# USB_CY7C68001-56LFC.net
KiCad netlist of a schematic drawn in Altium Designer
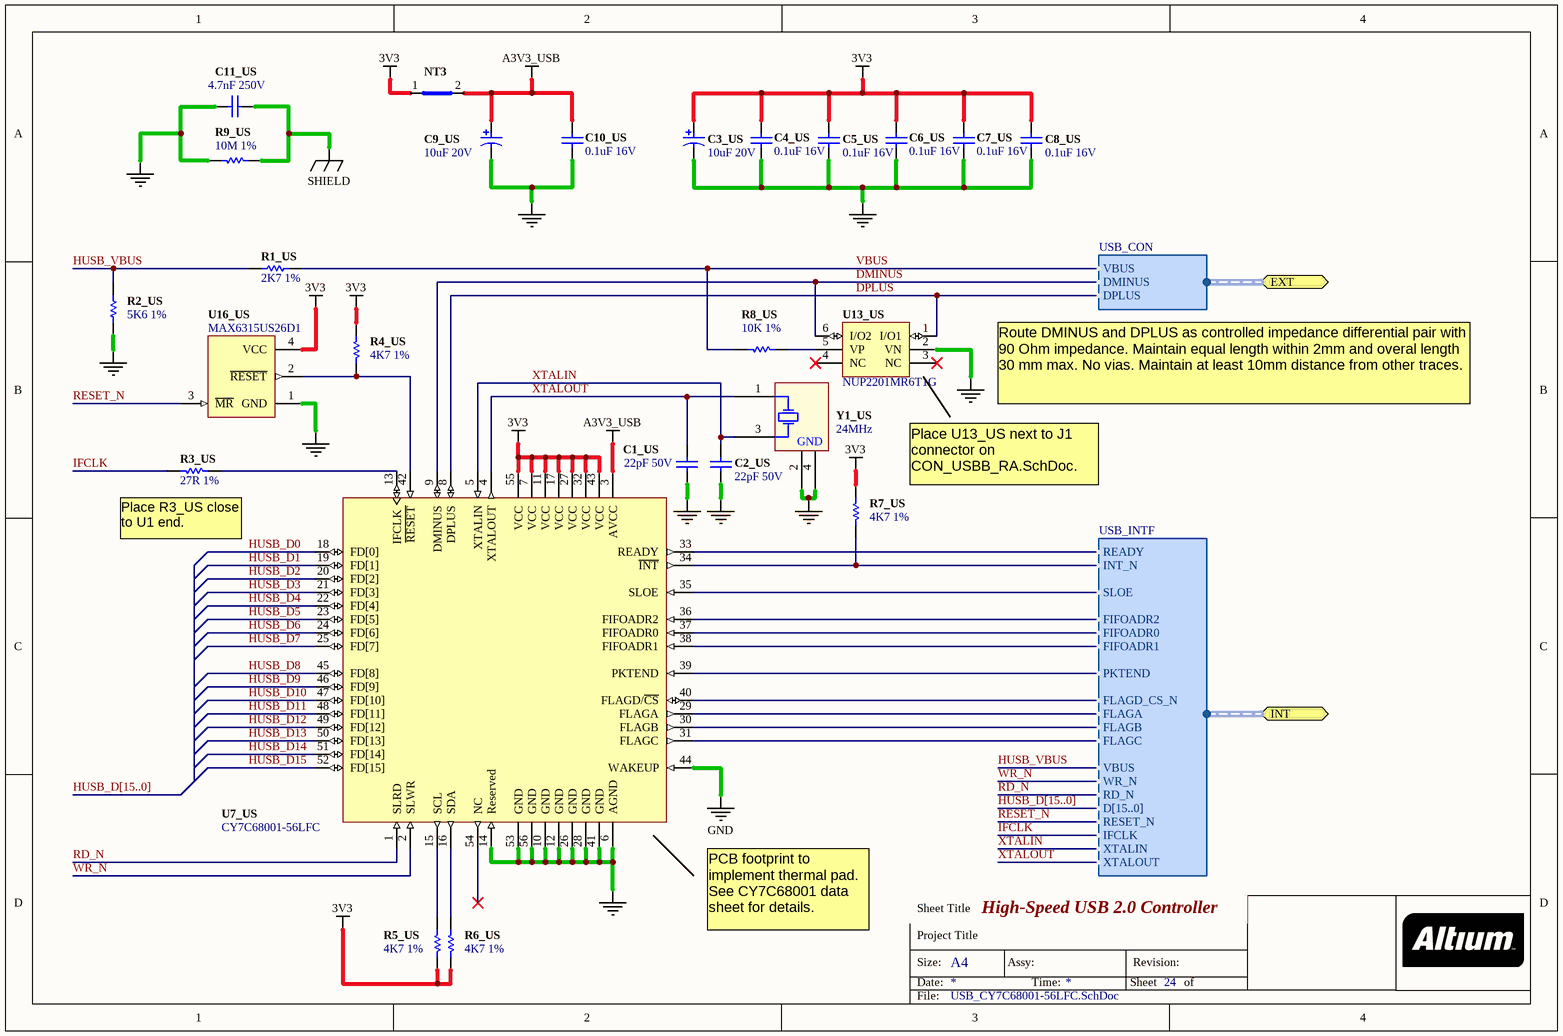
[diagram p0: USB_CY7C68001-56LFC.SchDoc]

(export (version "E")
  (design (tool "Eeschema 10.0.6"))
  (components
    (comp (ref "C1_US")
      (value "22pF 50V")
      (footprint "CAPC1005-STAR")
      (description "Capacitor, Ceramic, 22pF 5% 50V 0402 (1005) COG")
      (fields (field (name "TOLERANCE") "5 %"))
      (libsource (lib "AltiumDesignLibrary") (part "CAP-NP"))
    )
    (comp (ref "C2_US")
      (value "22pF 50V")
      (footprint "CAPC1005-STAR")
      (description "Capacitor, Ceramic, 22pF 5% 50V 0402 (1005) COG")
      (fields (field (name "TOLERANCE") "5 %"))
      (libsource (lib "AltiumDesignLibrary") (part "CAP-NP"))
    )
    (comp (ref "C3_US")
      (value "10uF 20V")
      (footprint "CAPC3528-STAR")
      (description "Capacitor, Tantalum, 10uF 10% 20V MCCT-B (3528)")
      (fields (field (name "TOLERANCE") "10 %"))
      (libsource (lib "AltiumDesignLibrary") (part "CAP-P"))
    )
    (comp (ref "C4_US")
      (value "0.1uF 16V")
      (footprint "CAPC1005-STAR")
      (description "Capacitor, Ceramic, 0.1uF 10% 16V 0402 (1005) X7R")
      (fields (field (name "TOLERANCE") "10 %"))
      (libsource (lib "AltiumDesignLibrary") (part "CAP-NP"))
    )
    (comp (ref "C5_US")
      (value "0.1uF 16V")
      (footprint "CAPC1005-STAR")
      (description "Capacitor, Ceramic, 0.1uF 10% 16V 0402 (1005) X7R")
      (fields (field (name "TOLERANCE") "10 %"))
      (libsource (lib "AltiumDesignLibrary") (part "CAP-NP"))
    )
    (comp (ref "C6_US")
      (value "0.1uF 16V")
      (footprint "CAPC1005-STAR")
      (description "Capacitor, Ceramic, 0.1uF 10% 16V 0402 (1005) X7R")
      (fields (field (name "TOLERANCE") "10 %"))
      (libsource (lib "AltiumDesignLibrary") (part "CAP-NP"))
    )
    (comp (ref "C7_US")
      (value "0.1uF 16V")
      (footprint "CAPC1005-STAR")
      (description "Capacitor, Ceramic, 0.1uF 10% 16V 0402 (1005) X7R")
      (fields (field (name "TOLERANCE") "10 %"))
      (libsource (lib "AltiumDesignLibrary") (part "CAP-NP"))
    )
    (comp (ref "C8_US")
      (value "0.1uF 16V")
      (footprint "CAPC1005-STAR")
      (description "Capacitor, Ceramic, 0.1uF 10% 16V 0402 (1005) X7R")
      (fields (field (name "TOLERANCE") "10 %"))
      (libsource (lib "AltiumDesignLibrary") (part "CAP-NP"))
    )
    (comp (ref "C9_US")
      (value "10uF 20V")
      (footprint "CAPC3528-STAR")
      (description "Capacitor, Tantalum, 10uF 10% 20V MCCT-B (3528)")
      (fields (field (name "TOLERANCE") "10 %"))
      (libsource (lib "AltiumDesignLibrary") (part "CAP-P"))
    )
    (comp (ref "C10_US")
      (value "0.1uF 16V")
      (footprint "CAPC1005-STAR")
      (description "Capacitor, Ceramic, 0.1uF 10% 16V 0402 (1005) X7R")
      (fields (field (name "TOLERANCE") "10 %"))
      (libsource (lib "AltiumDesignLibrary") (part "CAP-NP"))
    )
    (comp (ref "C11_US")
      (value "4.7nF 250V")
      (footprint "CAPM7163")
      (description "Capacitor, Ceramic, 4.7nF 20% 250V Panasonic BC J Lead (CAPM7163) Y5V")
      (fields (field (name "TOLERANCE") "20% %"))
      (libsource (lib "AltiumDesignLibrary") (part "CAP-NP"))
    )
    (comp (ref "NT3")
      (value "Net Tie SMT2")
      (footprint "NETTIE-SMT2-31X51")
      (description "Net-Tie, Surface Mount, 2 x 1.6mm x 0.8mm SMT Pads - For 0.8mm Track")
      (libsource (lib "AltiumDesignLibrary") (part "NETTIE-SMT2"))
    )
    (comp (ref "R1_US")
      (value "2K7 1%")
      (footprint "RESC1005-STAR")
      (description "Resistor, 2K7 1% 0402 (1005)")
      (fields (field (name "TOLERANCE") "1 %"))
      (libsource (lib "AltiumDesignLibrary") (part "RES"))
    )
    (comp (ref "R2_US")
      (value "5K6 1%")
      (footprint "RESC1005-STAR")
      (description "Resistor, 5K6 1% 0402 (1005)")
      (fields (field (name "TOLERANCE") "1 %"))
      (libsource (lib "AltiumDesignLibrary") (part "RES"))
    )
    (comp (ref "R3_US")
      (value "27R 1%")
      (footprint "RESC1005-STAR")
      (description "Resistor, 27R 1% 0402 (1005)")
      (fields (field (name "TOLERANCE") "1 %"))
      (libsource (lib "AltiumDesignLibrary") (part "RES"))
    )
    (comp (ref "R4_US")
      (value "4K7 1%")
      (footprint "RESC1005-STAR")
      (description "Resistor, 4K7 1% 0402 (1005)")
      (fields (field (name "TOLERANCE") "1 %"))
      (libsource (lib "AltiumDesignLibrary") (part "RES"))
    )
    (comp (ref "R5_US")
      (value "4K7 1%")
      (footprint "RESC1005-STAR")
      (description "Resistor, 4K7 1% 0402 (1005)")
      (fields (field (name "TOLERANCE") "1 %"))
      (libsource (lib "AltiumDesignLibrary") (part "RES"))
    )
    (comp (ref "R6_US")
      (value "4K7 1%")
      (footprint "RESC1005-STAR")
      (description "Resistor, 4K7 1% 0402 (1005)")
      (fields (field (name "TOLERANCE") "1 %"))
      (libsource (lib "AltiumDesignLibrary") (part "RES"))
    )
    (comp (ref "R7_US")
      (value "4K7 1%")
      (footprint "RESC1005-STAR")
      (description "Resistor, 4K7 1% 0402 (1005)")
      (fields (field (name "TOLERANCE") "1 %"))
      (libsource (lib "AltiumDesignLibrary") (part "RES"))
    )
    (comp (ref "R8_US")
      (value "10K 1%")
      (footprint "RESC1005-STAR")
      (description "Resistor, 10K 1% 0402 (1005)")
      (fields (field (name "TOLERANCE") "1 %"))
      (libsource (lib "AltiumDesignLibrary") (part "RES"))
    )
    (comp (ref "R9_US")
      (value "10M 1%")
      (footprint "RESC3216")
      (description "Resistor, 10M 1%1206 (3216)")
      (fields (field (name "TOLERANCE") "1 %"))
      (libsource (lib "AltiumDesignLibrary") (part "RES"))
    )
    (comp (ref "U7_US")
      (value "CY7C68001-56LFC")
      (footprint "QFN50P800X800_HS-57")
      (description "CY7C68001-56LFC, EZ-USB SX2 High-Speed USB Interface")
      (libsource (lib "AltiumDesignLibrary") (part "CY7C68001-56LFC"))
    )
    (comp (ref "U13_US")
      (value "NUP2201MR6T1G")
      (footprint "TSOP95P275-6")
      (description "NUP2201MR6, Low Capacitance Diode Array, USB Protection")
      (libsource (lib "AltiumDesignLibrary") (part "NUP2201MR6"))
    )
    (comp (ref "U16_US")
      (value "MAX6315US26D1")
      (footprint "SOT143")
      (description "MAX6315, Open-Drain Output SOT Reset IC, Customized Reset Thresholds, Timeout Delays")
      (libsource (lib "AltiumDesignLibrary") (part "MAX6315"))
    )
    (comp (ref "Y1_US")
      (value "24MHz")
      (footprint "XTAL-200X126-4")
      (description "Crystal, SMD, 24.000000MHz Stab=30ppm 20.0pF")
      (libsource (lib "AltiumDesignLibrary") (part "CRYSTAL-200X126-4"))
    )
  )
  (nets
    (net (code "3") (name "/DMINUS") (class "Default")
      (node (ref "U13_US") (pin "6") (pinfunction "I/O2_6") (pintype "bidirectional"))
      (node (ref "U7_US") (pin "9") (pinfunction "DMINUS_9") (pintype "bidirectional"))
    )
    (net (code "4") (name "/DPLUS") (class "Default")
      (node (ref "U13_US") (pin "1") (pinfunction "I/O1_1") (pintype "bidirectional"))
      (node (ref "U7_US") (pin "8") (pinfunction "DPLUS_8") (pintype "bidirectional"))
    )
    (net (code "5") (name "/FIFOADR0") (class "Default")
      (node (ref "U7_US") (pin "37") (pinfunction "FIFOADR0_37") (pintype "input"))
    )
    (net (code "6") (name "/FIFOADR1") (class "Default")
      (node (ref "U7_US") (pin "38") (pinfunction "FIFOADR1_38") (pintype "input"))
    )
    (net (code "7") (name "/FIFOADR2") (class "Default")
      (node (ref "U7_US") (pin "36") (pinfunction "FIFOADR2_36") (pintype "input"))
    )
    (net (code "8") (name "/FLAGA") (class "Default")
      (node (ref "U7_US") (pin "29") (pinfunction "FLAGA_29") (pintype "output"))
    )
    (net (code "9") (name "/FLAGB") (class "Default")
      (node (ref "U7_US") (pin "30") (pinfunction "FLAGB_30") (pintype "output"))
    )
    (net (code "10") (name "/FLAGC") (class "Default")
      (node (ref "U7_US") (pin "31") (pinfunction "FLAGC_31") (pintype "output"))
    )
    (net (code "11") (name "/FLAGD_CS_N") (class "Default")
      (node (ref "U7_US") (pin "40") (pinfunction "FLAGD/~{CS}_40") (pintype "bidirectional"))
    )
    (net (code "12") (name "/HUSB_D0") (class "Default")
      (node (ref "U7_US") (pin "18") (pinfunction "FD[0]_18") (pintype "bidirectional"))
    )
    (net (code "13") (name "/HUSB_D1") (class "Default")
      (node (ref "U7_US") (pin "19") (pinfunction "FD[1]_19") (pintype "bidirectional"))
    )
    (net (code "14") (name "/HUSB_D2") (class "Default")
      (node (ref "U7_US") (pin "20") (pinfunction "FD[2]_20") (pintype "bidirectional"))
    )
    (net (code "15") (name "/HUSB_D3") (class "Default")
      (node (ref "U7_US") (pin "21") (pinfunction "FD[3]_21") (pintype "bidirectional"))
    )
    (net (code "16") (name "/HUSB_D4") (class "Default")
      (node (ref "U7_US") (pin "22") (pinfunction "FD[4]_22") (pintype "bidirectional"))
    )
    (net (code "17") (name "/HUSB_D5") (class "Default")
      (node (ref "U7_US") (pin "23") (pinfunction "FD[5]_23") (pintype "bidirectional"))
    )
    (net (code "18") (name "/HUSB_D6") (class "Default")
      (node (ref "U7_US") (pin "24") (pinfunction "FD[6]_24") (pintype "bidirectional"))
    )
    (net (code "19") (name "/HUSB_D7") (class "Default")
      (node (ref "U7_US") (pin "25") (pinfunction "FD[7]_25") (pintype "bidirectional"))
    )
    (net (code "20") (name "/HUSB_D8") (class "Default")
      (node (ref "U7_US") (pin "45") (pinfunction "FD[8]_45") (pintype "bidirectional"))
    )
    (net (code "21") (name "/HUSB_D9") (class "Default")
      (node (ref "U7_US") (pin "46") (pinfunction "FD[9]_46") (pintype "bidirectional"))
    )
    (net (code "22") (name "/HUSB_D10") (class "Default")
      (node (ref "U7_US") (pin "47") (pinfunction "FD[10]_47") (pintype "bidirectional"))
    )
    (net (code "23") (name "/HUSB_D11") (class "Default")
      (node (ref "U7_US") (pin "48") (pinfunction "FD[11]_48") (pintype "bidirectional"))
    )
    (net (code "24") (name "/HUSB_D12") (class "Default")
      (node (ref "U7_US") (pin "49") (pinfunction "FD[12]_49") (pintype "bidirectional"))
    )
    (net (code "25") (name "/HUSB_D13") (class "Default")
      (node (ref "U7_US") (pin "50") (pinfunction "FD[13]_50") (pintype "bidirectional"))
    )
    (net (code "26") (name "/HUSB_D14") (class "Default")
      (node (ref "U7_US") (pin "51") (pinfunction "FD[14]_51") (pintype "bidirectional"))
    )
    (net (code "27") (name "/HUSB_D15") (class "Default")
      (node (ref "U7_US") (pin "52") (pinfunction "FD[15]_52") (pintype "bidirectional"))
    )
    (net (code "29") (name "/HUSB_VBUS") (class "Default")
      (node (ref "R1_US") (pin "1") (pinfunction "1_1") (pintype "passive"))
      (node (ref "R2_US") (pin "1") (pinfunction "1_1") (pintype "passive"))
    )
    (net (code "30") (name "/IFCLK") (class "Default")
      (node (ref "R3_US") (pin "1") (pinfunction "1_1") (pintype "passive"))
    )
    (net (code "31") (name "/INT_N") (class "Default")
      (node (ref "R7_US") (pin "1") (pinfunction "1_1") (pintype "passive"))
      (node (ref "U7_US") (pin "34") (pinfunction "~{INT}_34") (pintype "output"))
    )
    (net (code "32") (name "/PKTEND") (class "Default")
      (node (ref "U7_US") (pin "39") (pinfunction "PKTEND_39") (pintype "input"))
    )
    (net (code "33") (name "/RD_N") (class "Default")
      (node (ref "U7_US") (pin "1") (pinfunction "SLRD_1") (pintype "input"))
    )
    (net (code "34") (name "/READY") (class "Default")
      (node (ref "U7_US") (pin "33") (pinfunction "READY_33") (pintype "output"))
    )
    (net (code "35") (name "/RESET_N") (class "Default")
      (node (ref "U16_US") (pin "3") (pinfunction "~{MR}_3") (pintype "input"))
    )
    (net (code "36") (name "/SLOE") (class "Default")
      (node (ref "U7_US") (pin "35") (pinfunction "SLOE_35") (pintype "input"))
    )
    (net (code "37") (name "/VBUS") (class "Default")
      (node (ref "R1_US") (pin "2") (pinfunction "2_2") (pintype "passive"))
      (node (ref "R8_US") (pin "1") (pinfunction "1_1") (pintype "passive"))
    )
    (net (code "38") (name "/WR_N") (class "Default")
      (node (ref "U7_US") (pin "2") (pinfunction "SLWR_2") (pintype "input"))
    )
    (net (code "39") (name "/XTALIN") (class "Default")
      (node (ref "C2_US") (pin "1") (pinfunction "1_1") (pintype "passive"))
      (node (ref "U7_US") (pin "5") (pinfunction "XTALIN_5") (pintype "input"))
      (node (ref "Y1_US") (pin "3") (pinfunction "X2_3") (pintype "passive"))
    )
    (net (code "40") (name "/XTALOUT") (class "Default")
      (node (ref "C1_US") (pin "1") (pinfunction "1_1") (pintype "passive"))
      (node (ref "U7_US") (pin "4") (pinfunction "XTALOUT_4") (pintype "output"))
      (node (ref "Y1_US") (pin "1") (pinfunction "X1_1") (pintype "passive"))
    )
    (net (code "43") (name "3V3") (class "Default")
      (node (ref "C3_US") (pin "1") (pinfunction "1_1") (pintype "passive"))
      (node (ref "C4_US") (pin "2") (pinfunction "2_2") (pintype "passive"))
      (node (ref "C5_US") (pin "1") (pinfunction "1_1") (pintype "passive"))
      (node (ref "C6_US") (pin "2") (pinfunction "2_2") (pintype "passive"))
      (node (ref "C7_US") (pin "2") (pinfunction "2_2") (pintype "passive"))
      (node (ref "C8_US") (pin "1") (pinfunction "1_1") (pintype "passive"))
      (node (ref "NT3") (pin "1") (pinfunction "Net1_1") (pintype "passive"))
      (node (ref "R4_US") (pin "2") (pinfunction "2_2") (pintype "passive"))
      (node (ref "R5_US") (pin "1") (pinfunction "1_1") (pintype "passive"))
      (node (ref "R6_US") (pin "1") (pinfunction "1_1") (pintype "passive"))
      (node (ref "R7_US") (pin "2") (pinfunction "2_2") (pintype "passive"))
      (node (ref "U16_US") (pin "4") (pinfunction "VCC_4") (pintype "power_in"))
      (node (ref "U7_US") (pin "11") (pinfunction "VCC_11") (pintype "power_in"))
      (node (ref "U7_US") (pin "17") (pinfunction "VCC_17") (pintype "power_in"))
      (node (ref "U7_US") (pin "27") (pinfunction "VCC_27") (pintype "power_in"))
      (node (ref "U7_US") (pin "32") (pinfunction "VCC_32") (pintype "power_in"))
      (node (ref "U7_US") (pin "43") (pinfunction "VCC_43") (pintype "power_in"))
      (node (ref "U7_US") (pin "55") (pinfunction "VCC_55") (pintype "power_in"))
      (node (ref "U7_US") (pin "7") (pinfunction "VCC_7") (pintype "power_in"))
    )
    (net (code "44") (name "A3V3_USB") (class "Default")
      (node (ref "C10_US") (pin "2") (pinfunction "2_2") (pintype "passive"))
      (node (ref "C9_US") (pin "1") (pinfunction "1_1") (pintype "passive"))
      (node (ref "NT3") (pin "2") (pinfunction "Net2_2") (pintype "passive"))
      (node (ref "U7_US") (pin "3") (pinfunction "AVCC_3") (pintype "power_in"))
    )
    (net (code "45") (name "GND") (class "Default")
      (node (ref "C10_US") (pin "1") (pinfunction "1_1") (pintype "passive"))
      (node (ref "C11_US") (pin "2") (pinfunction "2_2") (pintype "passive"))
      (node (ref "C1_US") (pin "2") (pinfunction "2_2") (pintype "passive"))
      (node (ref "C2_US") (pin "2") (pinfunction "2_2") (pintype "passive"))
      (node (ref "C3_US") (pin "2") (pinfunction "2_2") (pintype "passive"))
      (node (ref "C4_US") (pin "1") (pinfunction "1_1") (pintype "passive"))
      (node (ref "C5_US") (pin "2") (pinfunction "2_2") (pintype "passive"))
      (node (ref "C6_US") (pin "1") (pinfunction "1_1") (pintype "passive"))
      (node (ref "C7_US") (pin "1") (pinfunction "1_1") (pintype "passive"))
      (node (ref "C8_US") (pin "2") (pinfunction "2_2") (pintype "passive"))
      (node (ref "C9_US") (pin "2") (pinfunction "2_2") (pintype "passive"))
      (node (ref "R2_US") (pin "2") (pinfunction "2_2") (pintype "passive"))
      (node (ref "R9_US") (pin "2") (pinfunction "2_2") (pintype "passive"))
      (node (ref "U13_US") (pin "2") (pinfunction "VN_2") (pintype "power_in"))
      (node (ref "U16_US") (pin "1") (pinfunction "GND_1") (pintype "power_in"))
      (node (ref "U7_US") (pin "10") (pinfunction "GND_10") (pintype "power_in"))
      (node (ref "U7_US") (pin "12") (pinfunction "GND_12") (pintype "power_in"))
      (node (ref "U7_US") (pin "14") (pinfunction "Reserved_14") (pintype "input"))
      (node (ref "U7_US") (pin "26") (pinfunction "GND_26") (pintype "power_in"))
      (node (ref "U7_US") (pin "28") (pinfunction "GND_28") (pintype "power_in"))
      (node (ref "U7_US") (pin "41") (pinfunction "GND_41") (pintype "power_in"))
      (node (ref "U7_US") (pin "44") (pinfunction "WAKEUP_44") (pintype "input"))
      (node (ref "U7_US") (pin "53") (pinfunction "GND_53") (pintype "power_in"))
      (node (ref "U7_US") (pin "56") (pinfunction "GND_56") (pintype "power_in"))
      (node (ref "U7_US") (pin "6") (pinfunction "AGND_6") (pintype "power_in"))
      (node (ref "Y1_US") (pin "2") (pinfunction "GND_2") (pintype "passive"))
      (node (ref "Y1_US") (pin "4") (pinfunction "GND_4") (pintype "passive"))
    )
    (net (code "46") (name "Net-(U7_US-IFCLK)") (class "Default")
      (node (ref "R3_US") (pin "2") (pinfunction "2_2") (pintype "passive"))
      (node (ref "U7_US") (pin "13") (pinfunction "IFCLK_13") (pintype "bidirectional"))
    )
    (net (code "47") (name "Net-(U7_US-SCL)") (class "Default")
      (node (ref "R5_US") (pin "2") (pinfunction "2_2") (pintype "passive"))
      (node (ref "U7_US") (pin "15") (pinfunction "SCL_15") (pintype "output"))
    )
    (net (code "48") (name "Net-(U7_US-SDA)") (class "Default")
      (node (ref "R6_US") (pin "2") (pinfunction "2_2") (pintype "passive"))
      (node (ref "U7_US") (pin "16") (pinfunction "SDA_16") (pintype "output"))
    )
    (net (code "49") (name "Net-(U13_US-VP)") (class "Default")
      (node (ref "R8_US") (pin "2") (pinfunction "2_2") (pintype "passive"))
      (node (ref "U13_US") (pin "5") (pinfunction "VP_5") (pintype "power_in"))
    )
    (net (code "50") (name "Net-(U16_US-~{RESET})") (class "Default")
      (node (ref "R4_US") (pin "1") (pinfunction "1_1") (pintype "passive"))
      (node (ref "U16_US") (pin "2") (pinfunction "~{RESET}_2") (pintype "output"))
      (node (ref "U7_US") (pin "42") (pinfunction "~{RESET}_42") (pintype "input"))
    )
    (net (code "51") (name "SHIELD") (class "Default")
      (node (ref "C11_US") (pin "1") (pinfunction "1_1") (pintype "passive"))
      (node (ref "R9_US") (pin "1") (pinfunction "1_1") (pintype "passive"))
    )
    (net (code "52") (name "unconnected-(U7_US-NC-Pad54)") (class "Default")
      (node (ref "U7_US") (pin "54") (pinfunction "NC_54") (pintype "output+no_connect"))
    )
    (net (code "53") (name "unconnected-(U13_US-NC-Pad3)") (class "Default")
      (node (ref "U13_US") (pin "3") (pinfunction "NC_3") (pintype "passive+no_connect"))
    )
    (net (code "54") (name "unconnected-(U13_US-NC-Pad4)") (class "Default")
      (node (ref "U13_US") (pin "4") (pinfunction "NC_4") (pintype "passive+no_connect"))
    )
  )
)
